# hat.net
KiCad netlist of a schematic drawn in EAGLE
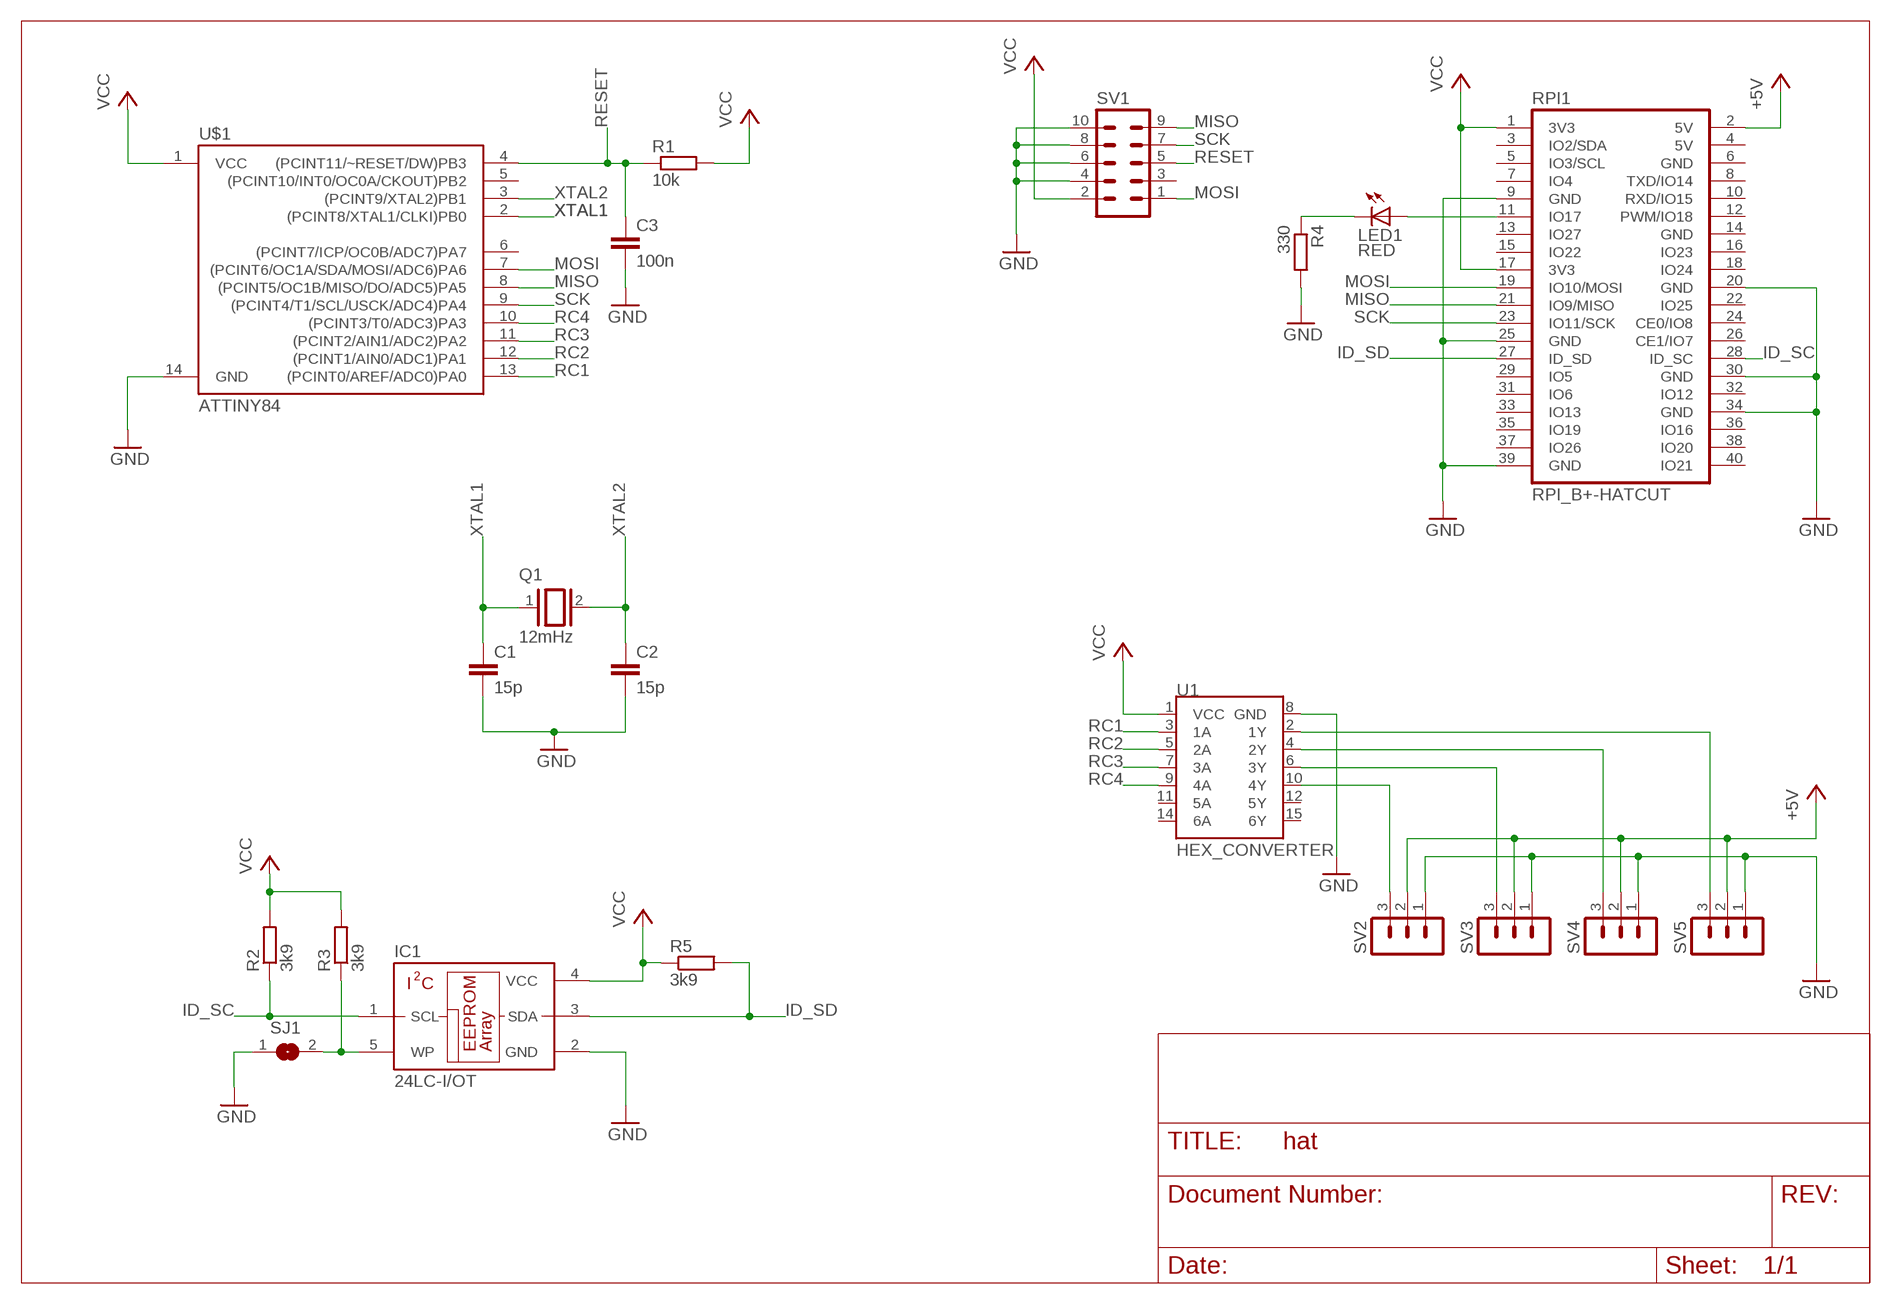
[diagram p0: schematic, sheet 1]

(export (version "E")
  (design (tool "Eeschema 10.0.6"))
  (components
    (comp (ref "C1")
      (value "15p")
      (footprint "eagle-import:C0603")
      (libsource (lib "eagle-import") (part "C-EUC0603"))
    )
    (comp (ref "C2")
      (value "15p")
      (footprint "eagle-import:C0603")
      (libsource (lib "eagle-import") (part "C-EUC0603"))
    )
    (comp (ref "C3")
      (value "100n")
      (footprint "eagle-import:C0603")
      (libsource (lib "eagle-import") (part "C-EUC0603"))
    )
    (comp (ref "IC1")
      (value "24LC-I/OT")
      (footprint "eagle-import:SOT23-5")
      (libsource (lib "eagle-import") (part "24LC-I/OT"))
    )
    (comp (ref "LED1")
      (value "RED")
      (footprint "eagle-import:CHIPLED_0805")
      (libsource (lib "eagle-import") (part "LEDCHIPLED_0805"))
    )
    (comp (ref "Q1")
      (value "12mHz")
      (footprint "eagle-import:QS")
      (libsource (lib "eagle-import") (part "XTAL/S"))
    )
    (comp (ref "R1")
      (value "10k")
      (footprint "eagle-import:R0805")
      (libsource (lib "eagle-import") (part "resistor_R-EU_R0805"))
    )
    (comp (ref "R2")
      (value "3k9")
      (footprint "eagle-import:R0805")
      (libsource (lib "eagle-import") (part "resistor_R-EU_R0805"))
    )
    (comp (ref "R3")
      (value "3k9")
      (footprint "eagle-import:R0805")
      (libsource (lib "eagle-import") (part "resistor_R-EU_R0805"))
    )
    (comp (ref "R4")
      (value "330")
      (footprint "eagle-import:R0805")
      (libsource (lib "eagle-import") (part "R-EU_R0805"))
    )
    (comp (ref "R5")
      (value "3k9")
      (footprint "eagle-import:R0805")
      (libsource (lib "eagle-import") (part "resistor_R-EU_R0805"))
    )
    (comp (ref "RPI1")
      (value "RPI_B+-HATCUT")
      (footprint "eagle-import:RPI-B+HAT_CUTOUT")
      (libsource (lib "eagle-import") (part "RPI_B+-HATCUT"))
    )
    (comp (ref "SJ1") (value "SJ") (footprint "eagle-import:SJ") (libsource (lib "eagle-import") (part "SJ")))
    (comp (ref "SV1")
      (value "MA05-2")
      (footprint "eagle-import:MA05-2")
      (libsource (lib "eagle-import") (part "MA05-2"))
    )
    (comp (ref "SV2")
      (value "MA03-1")
      (footprint "eagle-import:MA03-1")
      (libsource (lib "eagle-import") (part "MA03-1"))
    )
    (comp (ref "SV3")
      (value "MA03-1")
      (footprint "eagle-import:MA03-1")
      (libsource (lib "eagle-import") (part "MA03-1"))
    )
    (comp (ref "SV4")
      (value "MA03-1")
      (footprint "eagle-import:MA03-1")
      (libsource (lib "eagle-import") (part "MA03-1"))
    )
    (comp (ref "SV5")
      (value "MA03-1")
      (footprint "eagle-import:MA03-1")
      (libsource (lib "eagle-import") (part "MA03-1"))
    )
    (comp (ref "U$1")
      (value "ATTINY84")
      (footprint "eagle-import:SO14")
      (libsource (lib "eagle-import") (part "ATTINY84"))
    )
    (comp (ref "U1")
      (value "HEX_CONVERTER")
      (footprint "eagle-import:SO016")
      (libsource (lib "eagle-import") (part "HEX_CONVERTER"))
    )
  )
  (nets
    (net (code "1") (name "+5V") (class "Default")
      (node (ref "RPI1") (pin "2") (pinfunction "5V_2") (pintype "passive"))
      (node (ref "SV2") (pin "2") (pinfunction "2_2") (pintype "passive"))
      (node (ref "SV3") (pin "2") (pinfunction "2_2") (pintype "passive"))
      (node (ref "SV4") (pin "2") (pinfunction "2_2") (pintype "passive"))
      (node (ref "SV5") (pin "2") (pinfunction "2_2") (pintype "passive"))
    )
    (net (code "2") (name "/ID_SC") (class "Default")
      (node (ref "IC1") (pin "1") (pinfunction "SCL_1") (pintype "bidirectional"))
      (node (ref "R2") (pin "1") (pinfunction "1_1") (pintype "passive"))
      (node (ref "RPI1") (pin "28") (pinfunction "ID_SC_28") (pintype "bidirectional"))
    )
    (net (code "3") (name "/ID_SD") (class "Default")
      (node (ref "IC1") (pin "3") (pinfunction "SDA_3") (pintype "bidirectional"))
      (node (ref "R5") (pin "2") (pinfunction "2_2") (pintype "passive"))
      (node (ref "RPI1") (pin "27") (pinfunction "ID_SD_27") (pintype "bidirectional"))
    )
    (net (code "4") (name "/MISO") (class "Default")
      (node (ref "RPI1") (pin "21") (pinfunction "IO9/MISO_21") (pintype "passive"))
      (node (ref "SV1") (pin "9") (pinfunction "9_9") (pintype "passive"))
      (node (ref "U$1") (pin "8") (pinfunction "(PCINT5/OC1B/MISO/DO/ADC5)PA5_8") (pintype "bidirectional"))
    )
    (net (code "5") (name "/MOSI") (class "Default")
      (node (ref "RPI1") (pin "19") (pinfunction "IO10/MOSI_19") (pintype "passive"))
      (node (ref "SV1") (pin "1") (pinfunction "1_1") (pintype "passive"))
      (node (ref "U$1") (pin "7") (pinfunction "(PCINT6/OC1A/SDA/MOSI/ADC6)PA6_7") (pintype "bidirectional"))
    )
    (net (code "6") (name "/RC1") (class "Default")
      (node (ref "U$1") (pin "13") (pinfunction "(PCINT0/AREF/ADC0)PA0_13") (pintype "bidirectional"))
      (node (ref "U1") (pin "3") (pinfunction "1A_3") (pintype "bidirectional"))
    )
    (net (code "7") (name "/RC2") (class "Default")
      (node (ref "U$1") (pin "12") (pinfunction "(PCINT1/AIN0/ADC1)PA1_12") (pintype "bidirectional"))
      (node (ref "U1") (pin "5") (pinfunction "2A_5") (pintype "bidirectional"))
    )
    (net (code "8") (name "/RC3") (class "Default")
      (node (ref "U$1") (pin "11") (pinfunction "(PCINT2/AIN1/ADC2)PA2_11") (pintype "bidirectional"))
      (node (ref "U1") (pin "7") (pinfunction "3A_7") (pintype "bidirectional"))
    )
    (net (code "9") (name "/RC4") (class "Default")
      (node (ref "U$1") (pin "10") (pinfunction "(PCINT3/T0/ADC3)PA3_10") (pintype "bidirectional"))
      (node (ref "U1") (pin "9") (pinfunction "4A_9") (pintype "bidirectional"))
    )
    (net (code "10") (name "/RESET") (class "Default")
      (node (ref "C3") (pin "1") (pinfunction "1_1") (pintype "passive"))
      (node (ref "R1") (pin "1") (pinfunction "1_1") (pintype "passive"))
      (node (ref "SV1") (pin "5") (pinfunction "5_5") (pintype "passive"))
      (node (ref "U$1") (pin "4") (pinfunction "(PCINT11/~{RESET/DW})PB3_4") (pintype "bidirectional"))
    )
    (net (code "11") (name "/SCK") (class "Default")
      (node (ref "RPI1") (pin "23") (pinfunction "IO11/SCK_23") (pintype "passive"))
      (node (ref "SV1") (pin "7") (pinfunction "7_7") (pintype "passive"))
      (node (ref "U$1") (pin "9") (pinfunction "(PCINT4/T1/SCL/USCK/ADC4)PA4_9") (pintype "bidirectional"))
    )
    (net (code "12") (name "/XTAL1") (class "Default")
      (node (ref "C1") (pin "1") (pinfunction "1_1") (pintype "passive"))
      (node (ref "Q1") (pin "1") (pinfunction "1_1") (pintype "passive"))
      (node (ref "U$1") (pin "2") (pinfunction "(PCINT8/XTAL1/CLKI)PB0_2") (pintype "bidirectional"))
    )
    (net (code "13") (name "/XTAL2") (class "Default")
      (node (ref "C2") (pin "1") (pinfunction "1_1") (pintype "passive"))
      (node (ref "Q1") (pin "2") (pinfunction "2_2") (pintype "passive"))
      (node (ref "U$1") (pin "3") (pinfunction "(PCINT9/XTAL2)PB1_3") (pintype "bidirectional"))
    )
    (net (code "14") (name "GND") (class "Default")
      (node (ref "C1") (pin "2") (pinfunction "2_2") (pintype "passive"))
      (node (ref "C2") (pin "2") (pinfunction "2_2") (pintype "passive"))
      (node (ref "C3") (pin "2") (pinfunction "2_2") (pintype "passive"))
      (node (ref "IC1") (pin "2") (pinfunction "GND_2") (pintype "power_in"))
      (node (ref "R4") (pin "2") (pinfunction "2_2") (pintype "passive"))
      (node (ref "RPI1") (pin "20") (pinfunction "GND_20") (pintype "passive"))
      (node (ref "RPI1") (pin "25") (pinfunction "GND_25") (pintype "passive"))
      (node (ref "RPI1") (pin "30") (pinfunction "GND_30") (pintype "bidirectional"))
      (node (ref "RPI1") (pin "34") (pinfunction "GND_34") (pintype "bidirectional"))
      (node (ref "RPI1") (pin "39") (pinfunction "GND_39") (pintype "bidirectional"))
      (node (ref "RPI1") (pin "9") (pinfunction "GND_9") (pintype "passive"))
      (node (ref "SJ1") (pin "1") (pinfunction "1_1") (pintype "passive"))
      (node (ref "SV1") (pin "10") (pinfunction "10_10") (pintype "passive"))
      (node (ref "SV1") (pin "4") (pinfunction "4_4") (pintype "passive"))
      (node (ref "SV1") (pin "6") (pinfunction "6_6") (pintype "passive"))
      (node (ref "SV1") (pin "8") (pinfunction "8_8") (pintype "passive"))
      (node (ref "SV2") (pin "1") (pinfunction "1_1") (pintype "passive"))
      (node (ref "SV3") (pin "1") (pinfunction "1_1") (pintype "passive"))
      (node (ref "SV4") (pin "1") (pinfunction "1_1") (pintype "passive"))
      (node (ref "SV5") (pin "1") (pinfunction "1_1") (pintype "passive"))
      (node (ref "U$1") (pin "14") (pinfunction "GND_14") (pintype "bidirectional"))
      (node (ref "U1") (pin "8") (pinfunction "GND_8") (pintype "bidirectional"))
    )
    (net (code "15") (name "Net-(IC1-WP)") (class "Default")
      (node (ref "IC1") (pin "5") (pinfunction "WP_5") (pintype "bidirectional"))
      (node (ref "R3") (pin "1") (pinfunction "1_1") (pintype "passive"))
      (node (ref "SJ1") (pin "2") (pinfunction "2_2") (pintype "passive"))
    )
    (net (code "16") (name "Net-(LED1-PadC)") (class "Default")
      (node (ref "LED1") (pin "C") (pinfunction "C_C") (pintype "passive"))
      (node (ref "R4") (pin "1") (pinfunction "1_1") (pintype "passive"))
    )
    (net (code "17") (name "Net-(RPI1-IO17)") (class "Default")
      (node (ref "LED1") (pin "A") (pinfunction "A_A") (pintype "passive"))
      (node (ref "RPI1") (pin "11") (pinfunction "IO17_11") (pintype "passive"))
    )
    (net (code "18") (name "Net-(U1-1Y)") (class "Default")
      (node (ref "SV5") (pin "3") (pinfunction "3_3") (pintype "passive"))
      (node (ref "U1") (pin "2") (pinfunction "1Y_2") (pintype "bidirectional"))
    )
    (net (code "19") (name "Net-(U1-2Y)") (class "Default")
      (node (ref "SV4") (pin "3") (pinfunction "3_3") (pintype "passive"))
      (node (ref "U1") (pin "4") (pinfunction "2Y_4") (pintype "bidirectional"))
    )
    (net (code "20") (name "Net-(U1-3Y)") (class "Default")
      (node (ref "SV3") (pin "3") (pinfunction "3_3") (pintype "passive"))
      (node (ref "U1") (pin "6") (pinfunction "3Y_6") (pintype "bidirectional"))
    )
    (net (code "21") (name "Net-(U1-4Y)") (class "Default")
      (node (ref "SV2") (pin "3") (pinfunction "3_3") (pintype "passive"))
      (node (ref "U1") (pin "10") (pinfunction "4Y_10") (pintype "bidirectional"))
    )
    (net (code "22") (name "VCC") (class "Default")
      (node (ref "IC1") (pin "4") (pinfunction "VCC_4") (pintype "power_in"))
      (node (ref "R1") (pin "2") (pinfunction "2_2") (pintype "passive"))
      (node (ref "R2") (pin "2") (pinfunction "2_2") (pintype "passive"))
      (node (ref "R3") (pin "2") (pinfunction "2_2") (pintype "passive"))
      (node (ref "R5") (pin "1") (pinfunction "1_1") (pintype "passive"))
      (node (ref "RPI1") (pin "1") (pinfunction "3V3_1") (pintype "passive"))
      (node (ref "RPI1") (pin "17") (pinfunction "3V3_17") (pintype "passive"))
      (node (ref "SV1") (pin "2") (pinfunction "2_2") (pintype "passive"))
      (node (ref "U$1") (pin "1") (pinfunction "VCC_1") (pintype "bidirectional"))
      (node (ref "U1") (pin "1") (pinfunction "VCC_1") (pintype "bidirectional"))
    )
    (net (code "23") (name "unconnected-(RPI1-5V-Pad4)") (class "Default")
      (node (ref "RPI1") (pin "4") (pinfunction "5V_4") (pintype "passive"))
    )
    (net (code "24") (name "unconnected-(RPI1-CE0{slash}IO8-Pad24)") (class "Default")
      (node (ref "RPI1") (pin "24") (pinfunction "CE0/IO8_24") (pintype "passive"))
    )
    (net (code "25") (name "unconnected-(RPI1-CE1{slash}IO7-Pad26)") (class "Default")
      (node (ref "RPI1") (pin "26") (pinfunction "CE1/IO7_26") (pintype "passive"))
    )
    (net (code "26") (name "unconnected-(RPI1-GND-Pad6)") (class "Default")
      (node (ref "RPI1") (pin "6") (pinfunction "GND_6") (pintype "passive"))
    )
    (net (code "27") (name "unconnected-(RPI1-GND-Pad14)") (class "Default")
      (node (ref "RPI1") (pin "14") (pinfunction "GND_14") (pintype "passive"))
    )
    (net (code "28") (name "unconnected-(RPI1-IO2{slash}SDA-Pad3)") (class "Default")
      (node (ref "RPI1") (pin "3") (pinfunction "IO2/SDA_3") (pintype "passive"))
    )
    (net (code "29") (name "unconnected-(RPI1-IO3{slash}SCL-Pad5)") (class "Default")
      (node (ref "RPI1") (pin "5") (pinfunction "IO3/SCL_5") (pintype "passive"))
    )
    (net (code "30") (name "unconnected-(RPI1-IO4-Pad7)") (class "Default")
      (node (ref "RPI1") (pin "7") (pinfunction "IO4_7") (pintype "passive"))
    )
    (net (code "31") (name "unconnected-(RPI1-IO5-Pad29)") (class "Default")
      (node (ref "RPI1") (pin "29") (pinfunction "IO5_29") (pintype "bidirectional"))
    )
    (net (code "32") (name "unconnected-(RPI1-IO6-Pad31)") (class "Default")
      (node (ref "RPI1") (pin "31") (pinfunction "IO6_31") (pintype "bidirectional"))
    )
    (net (code "33") (name "unconnected-(RPI1-IO12-Pad32)") (class "Default")
      (node (ref "RPI1") (pin "32") (pinfunction "IO12_32") (pintype "bidirectional"))
    )
    (net (code "34") (name "unconnected-(RPI1-IO13-Pad33)") (class "Default")
      (node (ref "RPI1") (pin "33") (pinfunction "IO13_33") (pintype "bidirectional"))
    )
    (net (code "35") (name "unconnected-(RPI1-IO16-Pad36)") (class "Default")
      (node (ref "RPI1") (pin "36") (pinfunction "IO16_36") (pintype "bidirectional"))
    )
    (net (code "36") (name "unconnected-(RPI1-IO19-Pad35)") (class "Default")
      (node (ref "RPI1") (pin "35") (pinfunction "IO19_35") (pintype "bidirectional"))
    )
    (net (code "37") (name "unconnected-(RPI1-IO20-Pad38)") (class "Default")
      (node (ref "RPI1") (pin "38") (pinfunction "IO20_38") (pintype "bidirectional"))
    )
    (net (code "38") (name "unconnected-(RPI1-IO21-Pad40)") (class "Default")
      (node (ref "RPI1") (pin "40") (pinfunction "IO21_40") (pintype "bidirectional"))
    )
    (net (code "39") (name "unconnected-(RPI1-IO22-Pad15)") (class "Default")
      (node (ref "RPI1") (pin "15") (pinfunction "IO22_15") (pintype "passive"))
    )
    (net (code "40") (name "unconnected-(RPI1-IO23-Pad16)") (class "Default")
      (node (ref "RPI1") (pin "16") (pinfunction "IO23_16") (pintype "passive"))
    )
    (net (code "41") (name "unconnected-(RPI1-IO24-Pad18)") (class "Default")
      (node (ref "RPI1") (pin "18") (pinfunction "IO24_18") (pintype "passive"))
    )
    (net (code "42") (name "unconnected-(RPI1-IO25-Pad22)") (class "Default")
      (node (ref "RPI1") (pin "22") (pinfunction "IO25_22") (pintype "passive"))
    )
    (net (code "43") (name "unconnected-(RPI1-IO26-Pad37)") (class "Default")
      (node (ref "RPI1") (pin "37") (pinfunction "IO26_37") (pintype "bidirectional"))
    )
    (net (code "44") (name "unconnected-(RPI1-IO27-Pad13)") (class "Default")
      (node (ref "RPI1") (pin "13") (pinfunction "IO27_13") (pintype "passive"))
    )
    (net (code "45") (name "unconnected-(RPI1-PWM{slash}IO18-Pad12)") (class "Default")
      (node (ref "RPI1") (pin "12") (pinfunction "PWM/IO18_12") (pintype "passive"))
    )
    (net (code "46") (name "unconnected-(RPI1-RXD{slash}IO15-Pad10)") (class "Default")
      (node (ref "RPI1") (pin "10") (pinfunction "RXD/IO15_10") (pintype "passive"))
    )
    (net (code "47") (name "unconnected-(RPI1-TXD{slash}IO14-Pad8)") (class "Default")
      (node (ref "RPI1") (pin "8") (pinfunction "TXD/IO14_8") (pintype "passive"))
    )
    (net (code "48") (name "unconnected-(SV1-Pad3)") (class "Default")
      (node (ref "SV1") (pin "3") (pinfunction "3_3") (pintype "passive"))
    )
    (net (code "49") (name "unconnected-(U$1-(PCINT7{slash}ICP{slash}OC0B{slash}ADC7)PA7-Pad6)") (class "Default")
      (node (ref "U$1") (pin "6") (pinfunction "(PCINT7/ICP/OC0B/ADC7)PA7_6") (pintype "bidirectional"))
    )
    (net (code "50") (name "unconnected-(U$1-(PCINT10{slash}INT0{slash}OC0A{slash}CKOUT)PB2-Pad5)") (class "Default")
      (node (ref "U$1") (pin "5") (pinfunction "(PCINT10/INT0/OC0A/CKOUT)PB2_5") (pintype "bidirectional"))
    )
    (net (code "51") (name "unconnected-(U1-5A-Pad11)") (class "Default")
      (node (ref "U1") (pin "11") (pinfunction "5A_11") (pintype "bidirectional"))
    )
    (net (code "52") (name "unconnected-(U1-5Y-Pad12)") (class "Default")
      (node (ref "U1") (pin "12") (pinfunction "5Y_12") (pintype "bidirectional"))
    )
    (net (code "53") (name "unconnected-(U1-6A-Pad14)") (class "Default")
      (node (ref "U1") (pin "14") (pinfunction "6A_14") (pintype "bidirectional"))
    )
    (net (code "54") (name "unconnected-(U1-6Y-Pad15)") (class "Default")
      (node (ref "U1") (pin "15") (pinfunction "6Y_15") (pintype "bidirectional"))
    )
  )
)
